# bmsMaster_lvpower.net
KiCad netlist of a schematic drawn in Altium Designer
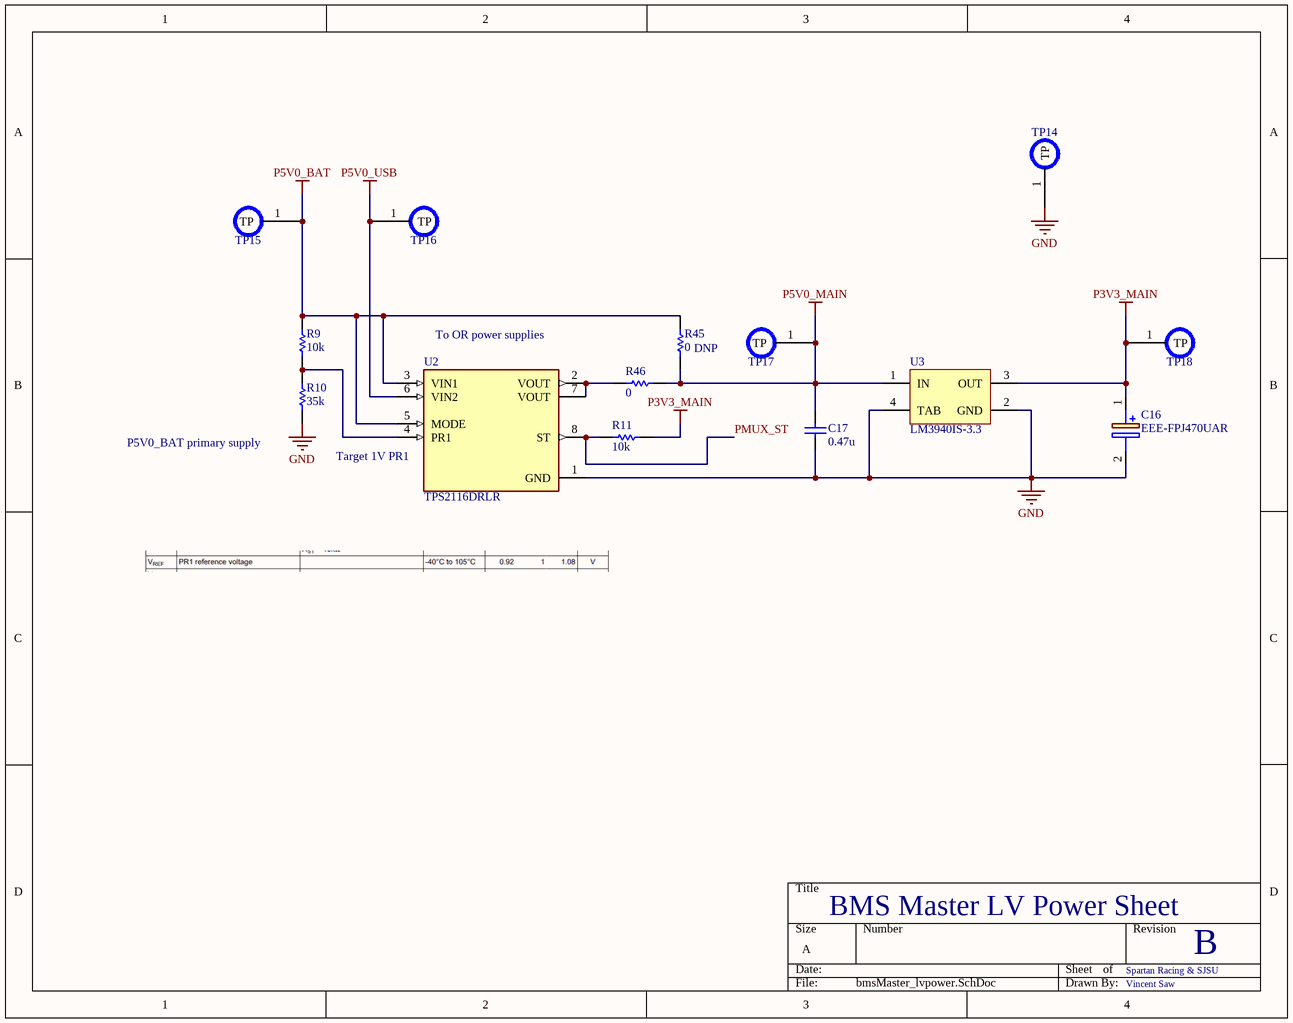
[diagram p0: bmsMaster_lvpower.SchDoc]

(export (version "E")
  (design (tool "Eeschema 10.0.6"))
  (components
    (comp (ref "C16")
      (value "EEE-FPJ470UAR")
      (footprint "SamacSys:EEE1AA220WR")
      (description "Capacitor Polarised")
      (fields (field (name "MOUSER PART NUMBER") "667-EEE-FPJ470UAR"))
      (libsource (lib "*") (part "EEE-FPJ470UAR"))
    )
    (comp (ref "C17")
      (value "0.47u")
      (footprint "CAPC1608X90N")
      (description "Capacitor")
      (libsource (lib "Simulation Generic Components") (part "Capacitor"))
    )
    (comp (ref "R9")
      (value "10k")
      (footprint "RESC1608X50N")
      (description "Resistor")
      (libsource (lib "Simulation Generic Components") (part "Resistor"))
    )
    (comp (ref "R10")
      (value "35k")
      (footprint "RESC1608X50N")
      (description "Resistor")
      (libsource (lib "Simulation Generic Components") (part "Resistor"))
    )
    (comp (ref "R11")
      (value "10k")
      (footprint "RESC1608X50N")
      (description "Resistor")
      (libsource (lib "Simulation Generic Components") (part "Resistor"))
    )
    (comp (ref "R45")
      (value "0")
      (footprint "RESC1608X50N")
      (description "Resistor")
      (libsource (lib "Simulation Generic Components") (part "Resistor"))
    )
    (comp (ref "R46")
      (value "0")
      (footprint "RESC1608X50N")
      (description "Resistor")
      (libsource (lib "Simulation Generic Components") (part "Resistor"))
    )
    (comp (ref "TP14")
      (value "TSTPT")
      (footprint "Testpoint1")
      (libsource (lib "testpoint1") (part "Testpoint1"))
    )
    (comp (ref "TP15")
      (value "TSTPT")
      (footprint "Testpoint1")
      (libsource (lib "testpoint1") (part "Testpoint1"))
    )
    (comp (ref "TP16")
      (value "TSTPT")
      (footprint "Testpoint1")
      (libsource (lib "testpoint1") (part "Testpoint1"))
    )
    (comp (ref "TP17")
      (value "TSTPT")
      (footprint "Testpoint1")
      (libsource (lib "testpoint1") (part "Testpoint1"))
    )
    (comp (ref "TP18")
      (value "TSTPT")
      (footprint "Testpoint1")
      (libsource (lib "testpoint1") (part "Testpoint1"))
    )
    (comp (ref "U2")
      (value "TPS2116DRLR")
      (footprint "TPS2116DRLR:SOTFL50P160X60-8N")
      (description "1.6 V to 5.5 V, 2.5-A Low IQ Power Mux with Manual and Priority Switchover")
      (fields (field (name "MF") "{'manufacturer': u'Texas Instruments'}"))
      (libsource (lib "TPS2116DRLR") (part "TPS2116DRLR"))
    )
    (comp (ref "U3")
      (value "LM3940IS-3.3")
      (footprint "KTT0003B_N")
      (description "1A Low Dropout Regulator for 5V to 3.3V Conversion, 3-pin TO-263")
      (fields (field (name "MANUFACTURER") "Texas Instruments"))
      (libsource (lib "Altium Content Vault") (part "PM-REG-LM2940-TO4"))
    )
  )
  (nets
    (net (code "1") (name "/PMUX_ST") (class "Default")
      (node (ref "R11") (pin "2") (pinfunction "2_2") (pintype "passive"))
      (node (ref "U2") (pin "8") (pinfunction "ST_8") (pintype "output"))
    )
    (net (code "2") (name "GND") (class "Default")
      (node (ref "C16") (pin "2") (pinfunction "-_2") (pintype "passive"))
      (node (ref "C17") (pin "1") (pinfunction "1_1") (pintype "passive"))
      (node (ref "R10") (pin "1") (pinfunction "1_1") (pintype "passive"))
      (node (ref "TP14") (pin "1") (pinfunction "TP_1") (pintype "passive"))
      (node (ref "U2") (pin "1") (pinfunction "GND_1") (pintype "power_in"))
      (node (ref "U3") (pin "2") (pinfunction "GND_2") (pintype "power_in"))
      (node (ref "U3") (pin "4") (pinfunction "TAB_4") (pintype "power_in"))
    )
    (net (code "3") (name "Net-(R46-Pad1)") (class "Default")
      (node (ref "R46") (pin "1") (pinfunction "1_1") (pintype "passive"))
      (node (ref "U2") (pin "2") (pinfunction "VOUT_2") (pintype "output"))
      (node (ref "U2") (pin "7") (pinfunction "VOUT_7") (pintype "passive"))
    )
    (net (code "4") (name "Net-(U2-PR1)") (class "Default")
      (node (ref "R10") (pin "2") (pinfunction "2_2") (pintype "passive"))
      (node (ref "R9") (pin "1") (pinfunction "1_1") (pintype "passive"))
      (node (ref "U2") (pin "4") (pinfunction "PR1_4") (pintype "input"))
    )
    (net (code "5") (name "P3V3_MAIN") (class "Default")
      (node (ref "C16") (pin "1") (pinfunction "+_1") (pintype "passive"))
      (node (ref "R11") (pin "1") (pinfunction "1_1") (pintype "passive"))
      (node (ref "TP18") (pin "1") (pinfunction "TP_1") (pintype "passive"))
      (node (ref "U3") (pin "3") (pinfunction "OUT_3") (pintype "power_in"))
    )
    (net (code "6") (name "P5V0_BAT") (class "Default")
      (node (ref "R45") (pin "2") (pinfunction "2_2") (pintype "passive"))
      (node (ref "R9") (pin "2") (pinfunction "2_2") (pintype "passive"))
      (node (ref "TP15") (pin "1") (pinfunction "TP_1") (pintype "passive"))
      (node (ref "U2") (pin "3") (pinfunction "VIN1_3") (pintype "input"))
      (node (ref "U2") (pin "5") (pinfunction "MODE_5") (pintype "input"))
    )
    (net (code "7") (name "P5V0_MAIN") (class "Default")
      (node (ref "C17") (pin "2") (pinfunction "2_2") (pintype "passive"))
      (node (ref "R45") (pin "1") (pinfunction "1_1") (pintype "passive"))
      (node (ref "R46") (pin "2") (pinfunction "2_2") (pintype "passive"))
      (node (ref "TP17") (pin "1") (pinfunction "TP_1") (pintype "passive"))
      (node (ref "U3") (pin "1") (pinfunction "IN_1") (pintype "power_in"))
    )
    (net (code "8") (name "P5V0_USB") (class "Default")
      (node (ref "TP16") (pin "1") (pinfunction "TP_1") (pintype "passive"))
      (node (ref "U2") (pin "6") (pinfunction "VIN2_6") (pintype "input"))
    )
  )
)
